# Main.net
KiCad netlist of a schematic drawn in Altium Designer
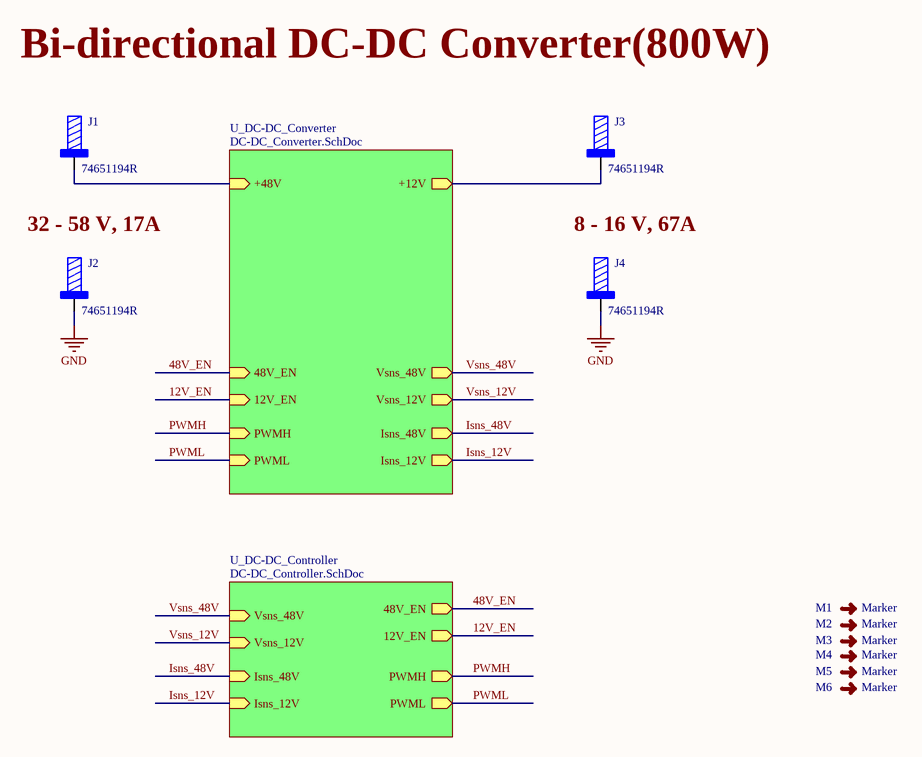
[diagram p0: Main.SchDoc]

(export (version "E")
  (design (tool "Eeschema 10.0.6"))
  (components
    (comp (ref "J1")
      (value "74651194R")
      (footprint "74651194")
      (description "WP-THRSH REDCUBE THR with external thread, M4 x 5mm, 85A")
      (fields (field (name "MANUFACTURER") "Wurth Elektronik"))
      (libsource (lib "WP-THRSH") (part "74651194R"))
    )
    (comp (ref "J2")
      (value "74651194R")
      (footprint "74651194")
      (description "WP-THRSH REDCUBE THR with external thread, M4 x 5mm, 85A")
      (fields (field (name "MANUFACTURER") "Wurth Elektronik"))
      (libsource (lib "WP-THRSH") (part "74651194R"))
    )
    (comp (ref "J3")
      (value "74651194R")
      (footprint "74651194")
      (description "WP-THRSH REDCUBE THR with external thread, M4 x 5mm, 85A")
      (fields (field (name "MANUFACTURER") "Wurth Elektronik"))
      (libsource (lib "WP-THRSH") (part "74651194R"))
    )
    (comp (ref "J4")
      (value "74651194R")
      (footprint "74651194")
      (description "WP-THRSH REDCUBE THR with external thread, M4 x 5mm, 85A")
      (fields (field (name "MANUFACTURER") "Wurth Elektronik"))
      (libsource (lib "WP-THRSH") (part "74651194R"))
    )
    (comp (ref "M1") (value "Marker") (footprint "PASSER-KREIS") (libsource (lib "*") (part "M")))
    (comp (ref "M2") (value "Marker") (footprint "PASSER-KREIS") (libsource (lib "*") (part "M")))
    (comp (ref "M3") (value "Marker") (footprint "PASSER-KREIS") (libsource (lib "*") (part "M")))
    (comp (ref "M4") (value "Marker") (footprint "PASSER-KREIS") (libsource (lib "*") (part "M")))
    (comp (ref "M5") (value "Marker") (footprint "PASSER-KREIS") (libsource (lib "*") (part "M")))
    (comp (ref "M6") (value "Marker") (footprint "PASSER-KREIS") (libsource (lib "*") (part "M")))
  )
  (nets
    (net (code "1") (name "/+12V") (class "Default")
      (node (ref "J3") (pin "1") (pinfunction "1_1") (pintype "passive"))
    )
    (net (code "2") (name "/+48V") (class "Default")
      (node (ref "J1") (pin "1") (pinfunction "1_1") (pintype "passive"))
    )
    (net (code "11") (name "GND") (class "Default")
      (node (ref "J2") (pin "1") (pinfunction "1_1") (pintype "passive"))
      (node (ref "J4") (pin "1") (pinfunction "1_1") (pintype "passive"))
    )
  )
)
